# OP1_1.net
KiCad netlist of a schematic drawn in EasyEDA
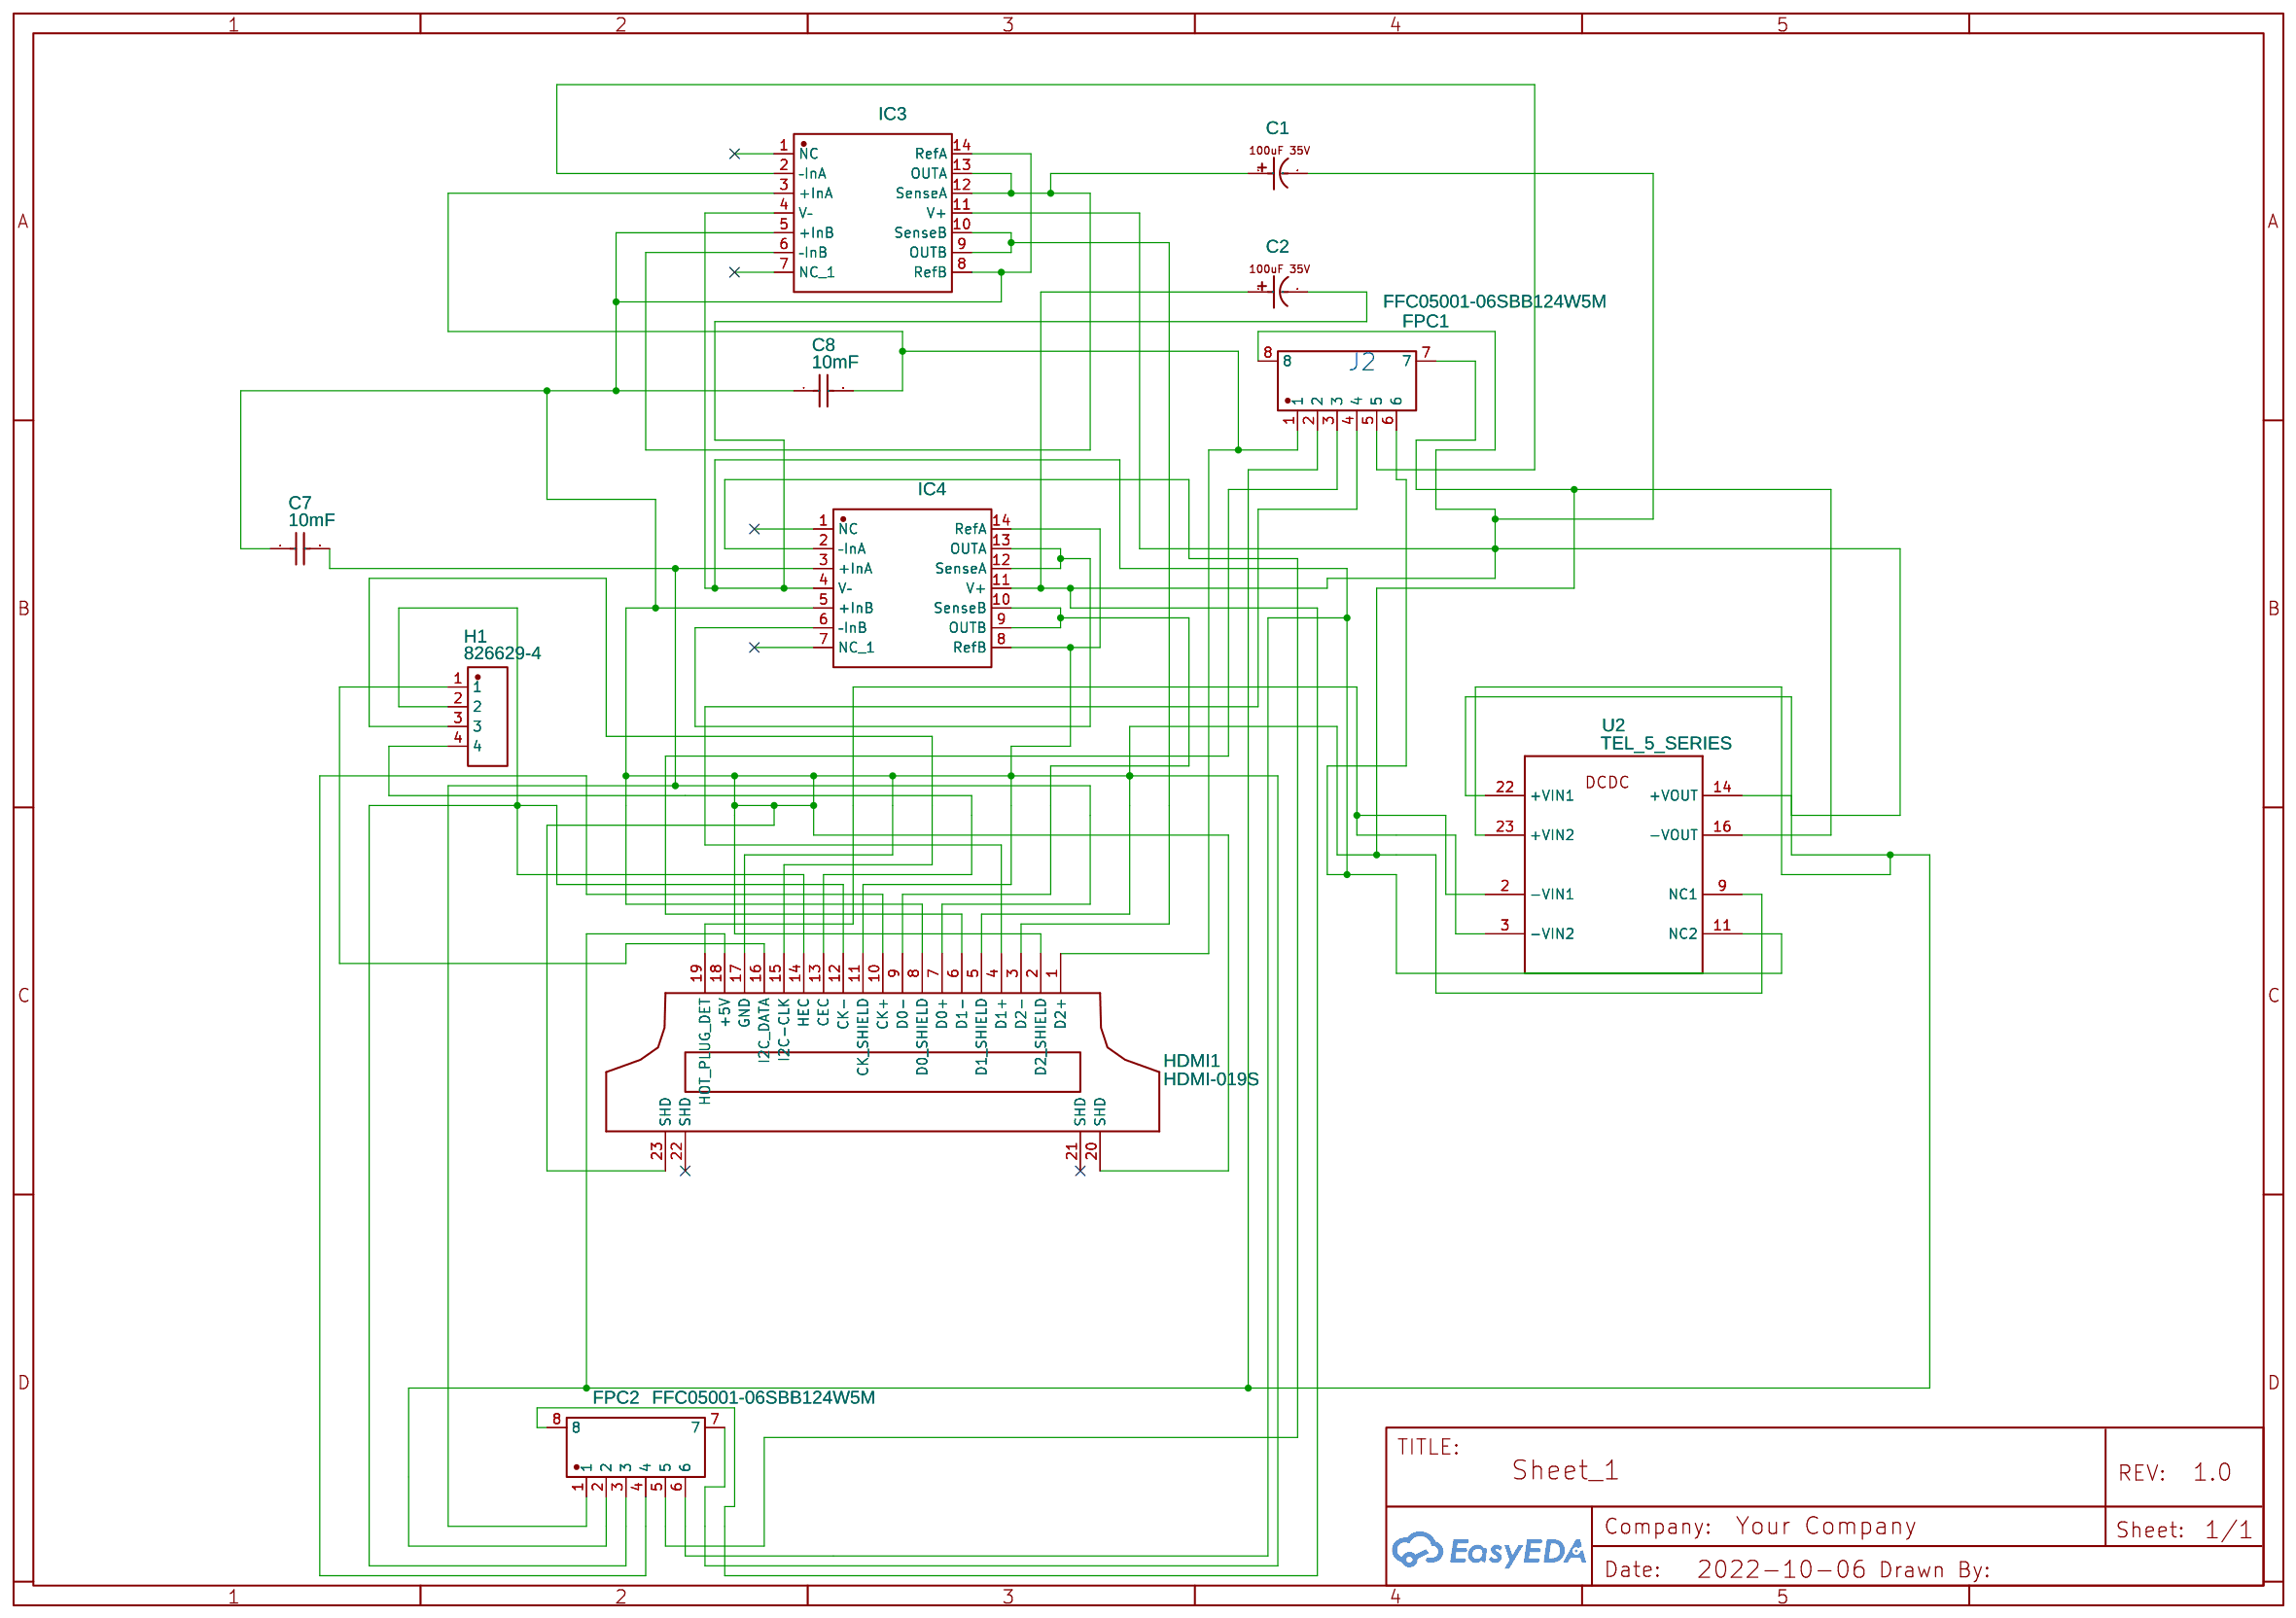
[diagram p0: schematic sheet]

(export (version "E")
  (design (tool "Eeschema 10.0.6"))
  (components
    (comp (ref "C1")
      (value "CONDENSATORE ELETTROLITICO 35V")
      (fields (field (name "BOM_Manufacturer Part") "100uF 35V"))
      (libsource (lib "") (part "CONDENSATORE ELETTROLITICO 35V"))
    )
    (comp (ref "C2")
      (value "CONDENSATORE ELETTROLITICO 35V")
      (fields (field (name "BOM_Manufacturer Part") "100uF 35V"))
      (libsource (lib "") (part "CONDENSATORE ELETTROLITICO 35V"))
    )
    (comp (ref "C7")
      (value "10mF")
      (fields
        (field (name "BOM_Manufacturer Part") "GRM43DR72J104KW01L")
        (field (name "BOM_Supplier Part") "C23743")
      )
      (libsource (lib "") (part "GRM43DR72J104KW01L"))
    )
    (comp (ref "C8")
      (value "10mF")
      (fields
        (field (name "BOM_Manufacturer Part") "GRM43DR72J104KW01L")
        (field (name "BOM_Supplier Part") "C23743")
      )
      (libsource (lib "") (part "GRM43DR72J104KW01L"))
    )
    (comp (ref "FPC1")
      (value "FFC05001-06SBB124W5M")
      (fields (field (name "BOM_Supplier Part") "C2834005"))
      (libsource (lib "") (part "FFC05001-06SBB124W5M"))
    )
    (comp (ref "FPC2")
      (value "FFC05001-06SBB124W5M")
      (fields (field (name "BOM_Supplier Part") "C2834005"))
      (libsource (lib "") (part "FFC05001-06SBB124W5M"))
    )
    (comp (ref "H1")
      (value "826629-4")
      (fields (field (name "BOM_Supplier Part") "C590277"))
      (libsource (lib "") (part "826629-4"))
    )
    (comp (ref "HDMI1")
      (value "HDMI-019S")
      (fields (field (name "BOM_Supplier Part") "C111617"))
      (libsource (lib "") (part "HDMI-019S"))
    )
    (comp (ref "IC3")
      (value "INA2133UA")
      (fields (field (name "BOM_Supplier Part") "C1347330"))
      (libsource (lib "") (part "INA2133UA"))
    )
    (comp (ref "IC4")
      (value "INA2133UA")
      (fields (field (name "BOM_Supplier Part") "C1347330"))
      (libsource (lib "") (part "INA2133UA"))
    )
    (comp (ref "U2") (value "TEL_5_SERIES") (libsource (lib "") (part "TEL_5_SERIES")))
  )
  (nets
    (net (code "1") (name "Net-(HDMI1-+5V)") (class "Default")
      (node (ref "FPC1") (pin "2") (pinfunction "2_2") (pintype "unspecified"))
      (node (ref "FPC2") (pin "2") (pinfunction "2_2") (pintype "unspecified"))
      (node (ref "HDMI1") (pin "18") (pinfunction "+5V_18") (pintype "unspecified"))
      (node (ref "U2") (pin "22") (pinfunction "+VIN1_22") (pintype "input"))
      (node (ref "U2") (pin "23") (pinfunction "+VIN2_23") (pintype "input"))
    )
    (net (code "2") (name "Net-(HDMI1-CEC)") (class "Default")
      (node (ref "H1") (pin "4") (pinfunction "4_4") (pintype "unspecified"))
      (node (ref "HDMI1") (pin "13") (pinfunction "CEC_13") (pintype "unspecified"))
    )
    (net (code "3") (name "Net-(HDMI1-CK+)") (class "Default")
      (node (ref "FPC2") (pin "4") (pinfunction "4_4") (pintype "unspecified"))
      (node (ref "HDMI1") (pin "10") (pinfunction "CK+_10") (pintype "unspecified"))
    )
    (net (code "4") (name "Net-(HDMI1-CK-)") (class "Default")
      (node (ref "FPC2") (pin "3") (pinfunction "3_3") (pintype "unspecified"))
      (node (ref "H1") (pin "2") (pinfunction "2_2") (pintype "unspecified"))
      (node (ref "HDMI1") (pin "12") (pinfunction "CK-_12") (pintype "unspecified"))
      (node (ref "HDMI1") (pin "14") (pinfunction "HEC_14") (pintype "unspecified"))
    )
    (net (code "5") (name "Net-(HDMI1-CK_SHIELD)") (class "Default")
      (node (ref "C7") (pin "1") (pinfunction "1_1") (pintype "input"))
      (node (ref "C8") (pin "1") (pinfunction "1_1") (pintype "input"))
      (node (ref "FPC1") (pin "7") (pinfunction "7_7") (pintype "unspecified"))
      (node (ref "FPC2") (pin "7") (pinfunction "7_7") (pintype "unspecified"))
      (node (ref "HDMI1") (pin "11") (pinfunction "CK_SHIELD_11") (pintype "unspecified"))
      (node (ref "HDMI1") (pin "17") (pinfunction "GND_17") (pintype "unspecified"))
      (node (ref "HDMI1") (pin "2") (pinfunction "D2_SHIELD_2") (pintype "unspecified"))
      (node (ref "HDMI1") (pin "20") (pinfunction "SHD_20") (pintype "unspecified"))
      (node (ref "HDMI1") (pin "23") (pinfunction "SHD_23") (pintype "unspecified"))
      (node (ref "HDMI1") (pin "5") (pinfunction "D1_SHIELD_5") (pintype "unspecified"))
      (node (ref "HDMI1") (pin "8") (pinfunction "D0_SHIELD_8") (pintype "unspecified"))
      (node (ref "IC3") (pin "14") (pinfunction "RefA_14") (pintype "unspecified"))
      (node (ref "IC3") (pin "5") (pinfunction "+InB_5") (pintype "unspecified"))
      (node (ref "IC3") (pin "8") (pinfunction "RefB_8") (pintype "unspecified"))
      (node (ref "IC4") (pin "14") (pinfunction "RefA_14") (pintype "unspecified"))
      (node (ref "IC4") (pin "5") (pinfunction "+InB_5") (pintype "unspecified"))
      (node (ref "IC4") (pin "8") (pinfunction "RefB_8") (pintype "unspecified"))
      (node (ref "U2") (pin "16") (pinfunction "-VOUT_16") (pintype "unspecified"))
      (node (ref "U2") (pin "9") (pinfunction "NC1_9") (pintype "unspecified"))
    )
    (net (code "6") (name "Net-(HDMI1-D0+)") (class "Default")
      (node (ref "C7") (pin "2") (pinfunction "2_2") (pintype "input"))
      (node (ref "FPC2") (pin "1") (pinfunction "1_1") (pintype "unspecified"))
      (node (ref "HDMI1") (pin "7") (pinfunction "D0+_7") (pintype "unspecified"))
      (node (ref "IC4") (pin "3") (pinfunction "+InA_3") (pintype "unspecified"))
    )
    (net (code "7") (name "Net-(HDMI1-D0-)") (class "Default")
      (node (ref "HDMI1") (pin "9") (pinfunction "D0-_9") (pintype "unspecified"))
      (node (ref "IC4") (pin "10") (pinfunction "SenseB_10") (pintype "unspecified"))
      (node (ref "IC4") (pin "9") (pinfunction "OUTB_9") (pintype "unspecified"))
    )
    (net (code "8") (name "Net-(HDMI1-D1+)") (class "Default")
      (node (ref "FPC1") (pin "4") (pinfunction "4_4") (pintype "unspecified"))
      (node (ref "HDMI1") (pin "4") (pinfunction "D1+_4") (pintype "unspecified"))
    )
    (net (code "9") (name "Net-(HDMI1-D1-)") (class "Default")
      (node (ref "FPC1") (pin "3") (pinfunction "3_3") (pintype "unspecified"))
      (node (ref "HDMI1") (pin "6") (pinfunction "D1-_6") (pintype "unspecified"))
    )
    (net (code "10") (name "Net-(HDMI1-D2+)") (class "Default")
      (node (ref "C8") (pin "2") (pinfunction "2_2") (pintype "input"))
      (node (ref "FPC1") (pin "1") (pinfunction "1_1") (pintype "unspecified"))
      (node (ref "HDMI1") (pin "1") (pinfunction "D2+_1") (pintype "unspecified"))
      (node (ref "IC3") (pin "3") (pinfunction "+InA_3") (pintype "unspecified"))
    )
    (net (code "11") (name "Net-(HDMI1-D2-)") (class "Default")
      (node (ref "HDMI1") (pin "3") (pinfunction "D2-_3") (pintype "unspecified"))
      (node (ref "IC3") (pin "10") (pinfunction "SenseB_10") (pintype "unspecified"))
      (node (ref "IC3") (pin "9") (pinfunction "OUTB_9") (pintype "unspecified"))
    )
    (net (code "12") (name "Net-(HDMI1-HOT_PLUG_DET)") (class "Default")
      (node (ref "HDMI1") (pin "19") (pinfunction "HOT_PLUG_DET_19") (pintype "unspecified"))
      (node (ref "U2") (pin "2") (pinfunction "-VIN1_2") (pintype "input"))
      (node (ref "U2") (pin "3") (pinfunction "-VIN2_3") (pintype "input"))
    )
    (net (code "13") (name "Net-(HDMI1-I2C-CLK)") (class "Default")
      (node (ref "H1") (pin "3") (pinfunction "3_3") (pintype "unspecified"))
      (node (ref "HDMI1") (pin "15") (pinfunction "I2C-CLK_15") (pintype "unspecified"))
    )
    (net (code "14") (name "Net-(HDMI1-I2C_DATA)") (class "Default")
      (node (ref "H1") (pin "1") (pinfunction "1_1") (pintype "unspecified"))
      (node (ref "HDMI1") (pin "16") (pinfunction "I2C_DATA_16") (pintype "unspecified"))
    )
    (net (code "15") (name "Net-(IC3-OUTA)") (class "Default")
      (node (ref "C1") (pin "1") (pinfunction "1_1") (pintype "input"))
      (node (ref "IC3") (pin "12") (pinfunction "SenseA_12") (pintype "unspecified"))
      (node (ref "IC3") (pin "13") (pinfunction "OUTA_13") (pintype "unspecified"))
      (node (ref "IC3") (pin "6") (pinfunction "–InB_6") (pintype "unspecified"))
    )
    (net (code "16") (name "Net-(IC3-V+)") (class "Default")
      (node (ref "C1") (pin "2") (pinfunction "2_2") (pintype "input"))
      (node (ref "C2") (pin "1") (pinfunction "1_1") (pintype "input"))
      (node (ref "FPC1") (pin "8") (pinfunction "8_8") (pintype "unspecified"))
      (node (ref "FPC2") (pin "8") (pinfunction "8_8") (pintype "unspecified"))
      (node (ref "IC3") (pin "11") (pinfunction "V+_11") (pintype "unspecified"))
      (node (ref "IC4") (pin "11") (pinfunction "V+_11") (pintype "unspecified"))
      (node (ref "U2") (pin "14") (pinfunction "+VOUT_14") (pintype "unspecified"))
    )
    (net (code "17") (name "Net-(IC3-V–)") (class "Default")
      (node (ref "C2") (pin "2") (pinfunction "2_2") (pintype "input"))
      (node (ref "FPC1") (pin "6") (pinfunction "6_6") (pintype "unspecified"))
      (node (ref "FPC2") (pin "6") (pinfunction "6_6") (pintype "unspecified"))
      (node (ref "IC3") (pin "4") (pinfunction "V–_4") (pintype "unspecified"))
      (node (ref "IC4") (pin "4") (pinfunction "V–_4") (pintype "unspecified"))
      (node (ref "U2") (pin "11") (pinfunction "NC2_11") (pintype "unspecified"))
    )
    (net (code "18") (name "Net-(IC3-–InA)") (class "Default")
      (node (ref "FPC1") (pin "5") (pinfunction "5_5") (pintype "unspecified"))
      (node (ref "IC3") (pin "2") (pinfunction "–InA_2") (pintype "unspecified"))
    )
    (net (code "19") (name "Net-(IC4-OUTA)") (class "Default")
      (node (ref "IC4") (pin "12") (pinfunction "SenseA_12") (pintype "unspecified"))
      (node (ref "IC4") (pin "13") (pinfunction "OUTA_13") (pintype "unspecified"))
      (node (ref "IC4") (pin "6") (pinfunction "–InB_6") (pintype "unspecified"))
    )
    (net (code "20") (name "Net-(IC4-–InA)") (class "Default")
      (node (ref "FPC2") (pin "5") (pinfunction "5_5") (pintype "unspecified"))
      (node (ref "IC4") (pin "2") (pinfunction "–InA_2") (pintype "unspecified"))
    )
    (net (code "21") (name "unconnected-(HDMI1-SHD-Pad21)") (class "Default")
      (node (ref "HDMI1") (pin "21") (pinfunction "SHD_21") (pintype "unspecified+no_connect"))
    )
    (net (code "22") (name "unconnected-(HDMI1-SHD-Pad22)") (class "Default")
      (node (ref "HDMI1") (pin "22") (pinfunction "SHD_22") (pintype "unspecified+no_connect"))
    )
    (net (code "23") (name "unconnected-(IC3-NC-Pad1)") (class "Default")
      (node (ref "IC3") (pin "1") (pinfunction "NC_1") (pintype "unspecified+no_connect"))
    )
    (net (code "24") (name "unconnected-(IC3-NC_1-Pad7)") (class "Default")
      (node (ref "IC3") (pin "7") (pinfunction "NC_1_7") (pintype "unspecified+no_connect"))
    )
    (net (code "25") (name "unconnected-(IC4-NC-Pad1)") (class "Default")
      (node (ref "IC4") (pin "1") (pinfunction "NC_1") (pintype "unspecified+no_connect"))
    )
    (net (code "26") (name "unconnected-(IC4-NC_1-Pad7)") (class "Default")
      (node (ref "IC4") (pin "7") (pinfunction "NC_1_7") (pintype "unspecified+no_connect"))
    )
  )
)
